# Sheet2.net
KiCad netlist of a schematic drawn in Altium Designer
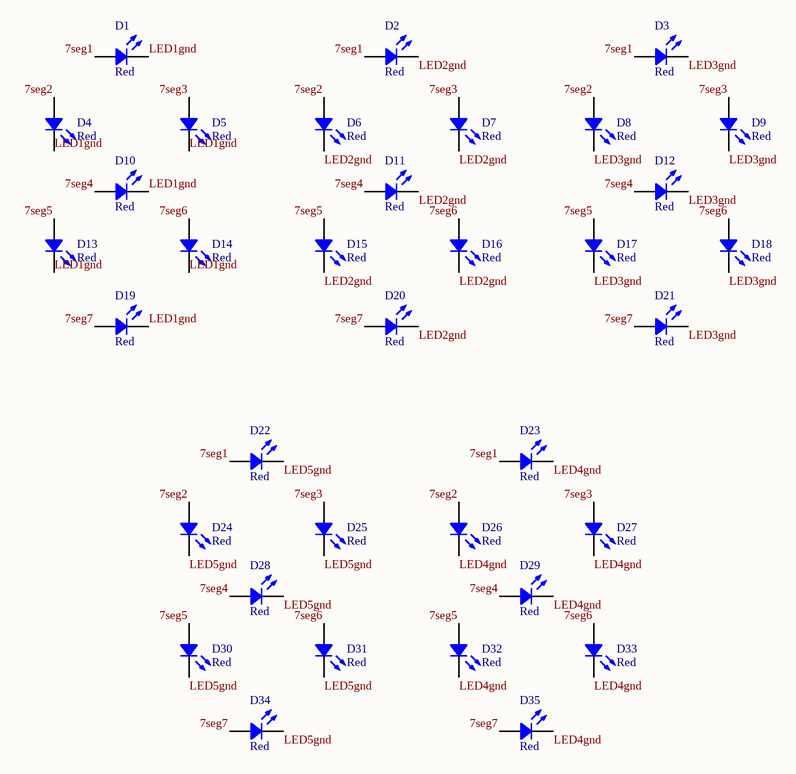
[diagram p0: Sheet2.SchDoc]

(export (version "E")
  (design (tool "Eeschema 10.0.6"))
  (components
    (comp (ref "D1")
      (value "Red")
      (footprint "LED 0805_2012 RED")
      (description "LED RED DIFFUSED SMD")
      (fields
        (field (name "PART NUMBER") "SML-LXT0805SRW-TR")
        (field (name "MANUFACTURER") "Lumex Opto/Components Inc.")
      )
      (libsource (lib "Celestial Altium Library - altium_library") (part "LED"))
    )
    (comp (ref "D2")
      (value "Red")
      (footprint "LED 0805_2012 RED")
      (description "LED RED DIFFUSED SMD")
      (fields
        (field (name "PART NUMBER") "SML-LXT0805SRW-TR")
        (field (name "MANUFACTURER") "Lumex Opto/Components Inc.")
      )
      (libsource (lib "Celestial Altium Library - altium_library") (part "LED"))
    )
    (comp (ref "D3")
      (value "Red")
      (footprint "LED 0805_2012 RED")
      (description "LED RED DIFFUSED SMD")
      (fields
        (field (name "PART NUMBER") "SML-LXT0805SRW-TR")
        (field (name "MANUFACTURER") "Lumex Opto/Components Inc.")
      )
      (libsource (lib "Celestial Altium Library - altium_library") (part "LED"))
    )
    (comp (ref "D4")
      (value "Red")
      (footprint "LED 0805_2012 RED")
      (description "LED RED DIFFUSED SMD")
      (fields
        (field (name "PART NUMBER") "SML-LXT0805SRW-TR")
        (field (name "MANUFACTURER") "Lumex Opto/Components Inc.")
      )
      (libsource (lib "Celestial Altium Library - altium_library") (part "LED"))
    )
    (comp (ref "D5")
      (value "Red")
      (footprint "LED 0805_2012 RED")
      (description "LED RED DIFFUSED SMD")
      (fields
        (field (name "PART NUMBER") "SML-LXT0805SRW-TR")
        (field (name "MANUFACTURER") "Lumex Opto/Components Inc.")
      )
      (libsource (lib "Celestial Altium Library - altium_library") (part "LED"))
    )
    (comp (ref "D6")
      (value "Red")
      (footprint "LED 0805_2012 RED")
      (description "LED RED DIFFUSED SMD")
      (fields
        (field (name "PART NUMBER") "SML-LXT0805SRW-TR")
        (field (name "MANUFACTURER") "Lumex Opto/Components Inc.")
      )
      (libsource (lib "Celestial Altium Library - altium_library") (part "LED"))
    )
    (comp (ref "D7")
      (value "Red")
      (footprint "LED 0805_2012 RED")
      (description "LED RED DIFFUSED SMD")
      (fields
        (field (name "PART NUMBER") "SML-LXT0805SRW-TR")
        (field (name "MANUFACTURER") "Lumex Opto/Components Inc.")
      )
      (libsource (lib "Celestial Altium Library - altium_library") (part "LED"))
    )
    (comp (ref "D8")
      (value "Red")
      (footprint "LED 0805_2012 RED")
      (description "LED RED DIFFUSED SMD")
      (fields
        (field (name "PART NUMBER") "SML-LXT0805SRW-TR")
        (field (name "MANUFACTURER") "Lumex Opto/Components Inc.")
      )
      (libsource (lib "Celestial Altium Library - altium_library") (part "LED"))
    )
    (comp (ref "D9")
      (value "Red")
      (footprint "LED 0805_2012 RED")
      (description "LED RED DIFFUSED SMD")
      (fields
        (field (name "PART NUMBER") "SML-LXT0805SRW-TR")
        (field (name "MANUFACTURER") "Lumex Opto/Components Inc.")
      )
      (libsource (lib "Celestial Altium Library - altium_library") (part "LED"))
    )
    (comp (ref "D10")
      (value "Red")
      (footprint "LED 0805_2012 RED")
      (description "LED RED DIFFUSED SMD")
      (fields
        (field (name "PART NUMBER") "SML-LXT0805SRW-TR")
        (field (name "MANUFACTURER") "Lumex Opto/Components Inc.")
      )
      (libsource (lib "Celestial Altium Library - altium_library") (part "LED"))
    )
    (comp (ref "D11")
      (value "Red")
      (footprint "LED 0805_2012 RED")
      (description "LED RED DIFFUSED SMD")
      (fields
        (field (name "PART NUMBER") "SML-LXT0805SRW-TR")
        (field (name "MANUFACTURER") "Lumex Opto/Components Inc.")
      )
      (libsource (lib "Celestial Altium Library - altium_library") (part "LED"))
    )
    (comp (ref "D12")
      (value "Red")
      (footprint "LED 0805_2012 RED")
      (description "LED RED DIFFUSED SMD")
      (fields
        (field (name "PART NUMBER") "SML-LXT0805SRW-TR")
        (field (name "MANUFACTURER") "Lumex Opto/Components Inc.")
      )
      (libsource (lib "Celestial Altium Library - altium_library") (part "LED"))
    )
    (comp (ref "D13")
      (value "Red")
      (footprint "LED 0805_2012 RED")
      (description "LED RED DIFFUSED SMD")
      (fields
        (field (name "PART NUMBER") "SML-LXT0805SRW-TR")
        (field (name "MANUFACTURER") "Lumex Opto/Components Inc.")
      )
      (libsource (lib "Celestial Altium Library - altium_library") (part "LED"))
    )
    (comp (ref "D14")
      (value "Red")
      (footprint "LED 0805_2012 RED")
      (description "LED RED DIFFUSED SMD")
      (fields
        (field (name "PART NUMBER") "SML-LXT0805SRW-TR")
        (field (name "MANUFACTURER") "Lumex Opto/Components Inc.")
      )
      (libsource (lib "Celestial Altium Library - altium_library") (part "LED"))
    )
    (comp (ref "D15")
      (value "Red")
      (footprint "LED 0805_2012 RED")
      (description "LED RED DIFFUSED SMD")
      (fields
        (field (name "PART NUMBER") "SML-LXT0805SRW-TR")
        (field (name "MANUFACTURER") "Lumex Opto/Components Inc.")
      )
      (libsource (lib "Celestial Altium Library - altium_library") (part "LED"))
    )
    (comp (ref "D16")
      (value "Red")
      (footprint "LED 0805_2012 RED")
      (description "LED RED DIFFUSED SMD")
      (fields
        (field (name "PART NUMBER") "SML-LXT0805SRW-TR")
        (field (name "MANUFACTURER") "Lumex Opto/Components Inc.")
      )
      (libsource (lib "Celestial Altium Library - altium_library") (part "LED"))
    )
    (comp (ref "D17")
      (value "Red")
      (footprint "LED 0805_2012 RED")
      (description "LED RED DIFFUSED SMD")
      (fields
        (field (name "PART NUMBER") "SML-LXT0805SRW-TR")
        (field (name "MANUFACTURER") "Lumex Opto/Components Inc.")
      )
      (libsource (lib "Celestial Altium Library - altium_library") (part "LED"))
    )
    (comp (ref "D18")
      (value "Red")
      (footprint "LED 0805_2012 RED")
      (description "LED RED DIFFUSED SMD")
      (fields
        (field (name "PART NUMBER") "SML-LXT0805SRW-TR")
        (field (name "MANUFACTURER") "Lumex Opto/Components Inc.")
      )
      (libsource (lib "Celestial Altium Library - altium_library") (part "LED"))
    )
    (comp (ref "D19")
      (value "Red")
      (footprint "LED 0805_2012 RED")
      (description "LED RED DIFFUSED SMD")
      (fields
        (field (name "PART NUMBER") "SML-LXT0805SRW-TR")
        (field (name "MANUFACTURER") "Lumex Opto/Components Inc.")
      )
      (libsource (lib "Celestial Altium Library - altium_library") (part "LED"))
    )
    (comp (ref "D20")
      (value "Red")
      (footprint "LED 0805_2012 RED")
      (description "LED RED DIFFUSED SMD")
      (fields
        (field (name "PART NUMBER") "SML-LXT0805SRW-TR")
        (field (name "MANUFACTURER") "Lumex Opto/Components Inc.")
      )
      (libsource (lib "Celestial Altium Library - altium_library") (part "LED"))
    )
    (comp (ref "D21")
      (value "Red")
      (footprint "LED 0805_2012 RED")
      (description "LED RED DIFFUSED SMD")
      (fields
        (field (name "PART NUMBER") "SML-LXT0805SRW-TR")
        (field (name "MANUFACTURER") "Lumex Opto/Components Inc.")
      )
      (libsource (lib "Celestial Altium Library - altium_library") (part "LED"))
    )
    (comp (ref "D22")
      (value "Red")
      (footprint "LED 0805_2012 RED")
      (description "LED RED DIFFUSED SMD")
      (fields
        (field (name "PART NUMBER") "SML-LXT0805SRW-TR")
        (field (name "MANUFACTURER") "Lumex Opto/Components Inc.")
      )
      (libsource (lib "Celestial Altium Library - altium_library") (part "LED"))
    )
    (comp (ref "D23")
      (value "Red")
      (footprint "LED 0805_2012 RED")
      (description "LED RED DIFFUSED SMD")
      (fields
        (field (name "PART NUMBER") "SML-LXT0805SRW-TR")
        (field (name "MANUFACTURER") "Lumex Opto/Components Inc.")
      )
      (libsource (lib "Celestial Altium Library - altium_library") (part "LED"))
    )
    (comp (ref "D24")
      (value "Red")
      (footprint "LED 0805_2012 RED")
      (description "LED RED DIFFUSED SMD")
      (fields
        (field (name "PART NUMBER") "SML-LXT0805SRW-TR")
        (field (name "MANUFACTURER") "Lumex Opto/Components Inc.")
      )
      (libsource (lib "Celestial Altium Library - altium_library") (part "LED"))
    )
    (comp (ref "D25")
      (value "Red")
      (footprint "LED 0805_2012 RED")
      (description "LED RED DIFFUSED SMD")
      (fields
        (field (name "PART NUMBER") "SML-LXT0805SRW-TR")
        (field (name "MANUFACTURER") "Lumex Opto/Components Inc.")
      )
      (libsource (lib "Celestial Altium Library - altium_library") (part "LED"))
    )
    (comp (ref "D26")
      (value "Red")
      (footprint "LED 0805_2012 RED")
      (description "LED RED DIFFUSED SMD")
      (fields
        (field (name "PART NUMBER") "SML-LXT0805SRW-TR")
        (field (name "MANUFACTURER") "Lumex Opto/Components Inc.")
      )
      (libsource (lib "Celestial Altium Library - altium_library") (part "LED"))
    )
    (comp (ref "D27")
      (value "Red")
      (footprint "LED 0805_2012 RED")
      (description "LED RED DIFFUSED SMD")
      (fields
        (field (name "PART NUMBER") "SML-LXT0805SRW-TR")
        (field (name "MANUFACTURER") "Lumex Opto/Components Inc.")
      )
      (libsource (lib "Celestial Altium Library - altium_library") (part "LED"))
    )
    (comp (ref "D28")
      (value "Red")
      (footprint "LED 0805_2012 RED")
      (description "LED RED DIFFUSED SMD")
      (fields
        (field (name "PART NUMBER") "SML-LXT0805SRW-TR")
        (field (name "MANUFACTURER") "Lumex Opto/Components Inc.")
      )
      (libsource (lib "Celestial Altium Library - altium_library") (part "LED"))
    )
    (comp (ref "D29")
      (value "Red")
      (footprint "LED 0805_2012 RED")
      (description "LED RED DIFFUSED SMD")
      (fields
        (field (name "PART NUMBER") "SML-LXT0805SRW-TR")
        (field (name "MANUFACTURER") "Lumex Opto/Components Inc.")
      )
      (libsource (lib "Celestial Altium Library - altium_library") (part "LED"))
    )
    (comp (ref "D30")
      (value "Red")
      (footprint "LED 0805_2012 RED")
      (description "LED RED DIFFUSED SMD")
      (fields
        (field (name "PART NUMBER") "SML-LXT0805SRW-TR")
        (field (name "MANUFACTURER") "Lumex Opto/Components Inc.")
      )
      (libsource (lib "Celestial Altium Library - altium_library") (part "LED"))
    )
    (comp (ref "D31")
      (value "Red")
      (footprint "LED 0805_2012 RED")
      (description "LED RED DIFFUSED SMD")
      (fields
        (field (name "PART NUMBER") "SML-LXT0805SRW-TR")
        (field (name "MANUFACTURER") "Lumex Opto/Components Inc.")
      )
      (libsource (lib "Celestial Altium Library - altium_library") (part "LED"))
    )
    (comp (ref "D32")
      (value "Red")
      (footprint "LED 0805_2012 RED")
      (description "LED RED DIFFUSED SMD")
      (fields
        (field (name "PART NUMBER") "SML-LXT0805SRW-TR")
        (field (name "MANUFACTURER") "Lumex Opto/Components Inc.")
      )
      (libsource (lib "Celestial Altium Library - altium_library") (part "LED"))
    )
    (comp (ref "D33")
      (value "Red")
      (footprint "LED 0805_2012 RED")
      (description "LED RED DIFFUSED SMD")
      (fields
        (field (name "PART NUMBER") "SML-LXT0805SRW-TR")
        (field (name "MANUFACTURER") "Lumex Opto/Components Inc.")
      )
      (libsource (lib "Celestial Altium Library - altium_library") (part "LED"))
    )
    (comp (ref "D34")
      (value "Red")
      (footprint "LED 0805_2012 RED")
      (description "LED RED DIFFUSED SMD")
      (fields
        (field (name "PART NUMBER") "SML-LXT0805SRW-TR")
        (field (name "MANUFACTURER") "Lumex Opto/Components Inc.")
      )
      (libsource (lib "Celestial Altium Library - altium_library") (part "LED"))
    )
    (comp (ref "D35")
      (value "Red")
      (footprint "LED 0805_2012 RED")
      (description "LED RED DIFFUSED SMD")
      (fields
        (field (name "PART NUMBER") "SML-LXT0805SRW-TR")
        (field (name "MANUFACTURER") "Lumex Opto/Components Inc.")
      )
      (libsource (lib "Celestial Altium Library - altium_library") (part "LED"))
    )
  )
  (nets
    (net (code "1") (name "/7seg1") (class "Default")
      (node (ref "D1") (pin "1") (pinfunction "1_1") (pintype "passive"))
      (node (ref "D2") (pin "1") (pinfunction "1_1") (pintype "passive"))
      (node (ref "D22") (pin "1") (pinfunction "1_1") (pintype "passive"))
      (node (ref "D23") (pin "1") (pinfunction "1_1") (pintype "passive"))
      (node (ref "D3") (pin "1") (pinfunction "1_1") (pintype "passive"))
    )
    (net (code "2") (name "/7seg2") (class "Default")
      (node (ref "D24") (pin "1") (pinfunction "1_1") (pintype "passive"))
      (node (ref "D26") (pin "1") (pinfunction "1_1") (pintype "passive"))
      (node (ref "D4") (pin "1") (pinfunction "1_1") (pintype "passive"))
      (node (ref "D6") (pin "1") (pinfunction "1_1") (pintype "passive"))
      (node (ref "D8") (pin "1") (pinfunction "1_1") (pintype "passive"))
    )
    (net (code "3") (name "/7seg3") (class "Default")
      (node (ref "D25") (pin "1") (pinfunction "1_1") (pintype "passive"))
      (node (ref "D27") (pin "1") (pinfunction "1_1") (pintype "passive"))
      (node (ref "D5") (pin "1") (pinfunction "1_1") (pintype "passive"))
      (node (ref "D7") (pin "1") (pinfunction "1_1") (pintype "passive"))
      (node (ref "D9") (pin "1") (pinfunction "1_1") (pintype "passive"))
    )
    (net (code "4") (name "/7seg4") (class "Default")
      (node (ref "D10") (pin "1") (pinfunction "1_1") (pintype "passive"))
      (node (ref "D11") (pin "1") (pinfunction "1_1") (pintype "passive"))
      (node (ref "D12") (pin "1") (pinfunction "1_1") (pintype "passive"))
      (node (ref "D28") (pin "1") (pinfunction "1_1") (pintype "passive"))
      (node (ref "D29") (pin "1") (pinfunction "1_1") (pintype "passive"))
    )
    (net (code "5") (name "/7seg5") (class "Default")
      (node (ref "D13") (pin "1") (pinfunction "1_1") (pintype "passive"))
      (node (ref "D15") (pin "1") (pinfunction "1_1") (pintype "passive"))
      (node (ref "D17") (pin "1") (pinfunction "1_1") (pintype "passive"))
      (node (ref "D30") (pin "1") (pinfunction "1_1") (pintype "passive"))
      (node (ref "D32") (pin "1") (pinfunction "1_1") (pintype "passive"))
    )
    (net (code "6") (name "/7seg6") (class "Default")
      (node (ref "D14") (pin "1") (pinfunction "1_1") (pintype "passive"))
      (node (ref "D16") (pin "1") (pinfunction "1_1") (pintype "passive"))
      (node (ref "D18") (pin "1") (pinfunction "1_1") (pintype "passive"))
      (node (ref "D31") (pin "1") (pinfunction "1_1") (pintype "passive"))
      (node (ref "D33") (pin "1") (pinfunction "1_1") (pintype "passive"))
    )
    (net (code "7") (name "/7seg7") (class "Default")
      (node (ref "D19") (pin "1") (pinfunction "1_1") (pintype "passive"))
      (node (ref "D20") (pin "1") (pinfunction "1_1") (pintype "passive"))
      (node (ref "D21") (pin "1") (pinfunction "1_1") (pintype "passive"))
      (node (ref "D34") (pin "1") (pinfunction "1_1") (pintype "passive"))
      (node (ref "D35") (pin "1") (pinfunction "1_1") (pintype "passive"))
    )
    (net (code "8") (name "/LED1gnd") (class "Default")
      (node (ref "D1") (pin "2") (pinfunction "2_2") (pintype "passive"))
      (node (ref "D10") (pin "2") (pinfunction "2_2") (pintype "passive"))
      (node (ref "D13") (pin "2") (pinfunction "2_2") (pintype "passive"))
      (node (ref "D14") (pin "2") (pinfunction "2_2") (pintype "passive"))
      (node (ref "D19") (pin "2") (pinfunction "2_2") (pintype "passive"))
      (node (ref "D4") (pin "2") (pinfunction "2_2") (pintype "passive"))
      (node (ref "D5") (pin "2") (pinfunction "2_2") (pintype "passive"))
    )
    (net (code "9") (name "/LED2gnd") (class "Default")
      (node (ref "D11") (pin "2") (pinfunction "2_2") (pintype "passive"))
      (node (ref "D15") (pin "2") (pinfunction "2_2") (pintype "passive"))
      (node (ref "D16") (pin "2") (pinfunction "2_2") (pintype "passive"))
      (node (ref "D2") (pin "2") (pinfunction "2_2") (pintype "passive"))
      (node (ref "D20") (pin "2") (pinfunction "2_2") (pintype "passive"))
      (node (ref "D6") (pin "2") (pinfunction "2_2") (pintype "passive"))
      (node (ref "D7") (pin "2") (pinfunction "2_2") (pintype "passive"))
    )
    (net (code "10") (name "/LED3gnd") (class "Default")
      (node (ref "D12") (pin "2") (pinfunction "2_2") (pintype "passive"))
      (node (ref "D17") (pin "2") (pinfunction "2_2") (pintype "passive"))
      (node (ref "D18") (pin "2") (pinfunction "2_2") (pintype "passive"))
      (node (ref "D21") (pin "2") (pinfunction "2_2") (pintype "passive"))
      (node (ref "D3") (pin "2") (pinfunction "2_2") (pintype "passive"))
      (node (ref "D8") (pin "2") (pinfunction "2_2") (pintype "passive"))
      (node (ref "D9") (pin "2") (pinfunction "2_2") (pintype "passive"))
    )
    (net (code "11") (name "/LED4gnd") (class "Default")
      (node (ref "D23") (pin "2") (pinfunction "2_2") (pintype "passive"))
      (node (ref "D26") (pin "2") (pinfunction "2_2") (pintype "passive"))
      (node (ref "D27") (pin "2") (pinfunction "2_2") (pintype "passive"))
      (node (ref "D29") (pin "2") (pinfunction "2_2") (pintype "passive"))
      (node (ref "D32") (pin "2") (pinfunction "2_2") (pintype "passive"))
      (node (ref "D33") (pin "2") (pinfunction "2_2") (pintype "passive"))
      (node (ref "D35") (pin "2") (pinfunction "2_2") (pintype "passive"))
    )
    (net (code "12") (name "/LED5gnd") (class "Default")
      (node (ref "D22") (pin "2") (pinfunction "2_2") (pintype "passive"))
      (node (ref "D24") (pin "2") (pinfunction "2_2") (pintype "passive"))
      (node (ref "D25") (pin "2") (pinfunction "2_2") (pintype "passive"))
      (node (ref "D28") (pin "2") (pinfunction "2_2") (pintype "passive"))
      (node (ref "D30") (pin "2") (pinfunction "2_2") (pintype "passive"))
      (node (ref "D31") (pin "2") (pinfunction "2_2") (pintype "passive"))
      (node (ref "D34") (pin "2") (pinfunction "2_2") (pintype "passive"))
    )
  )
)
